# M112X.net
KiCad netlist of a schematic drawn in EAGLE
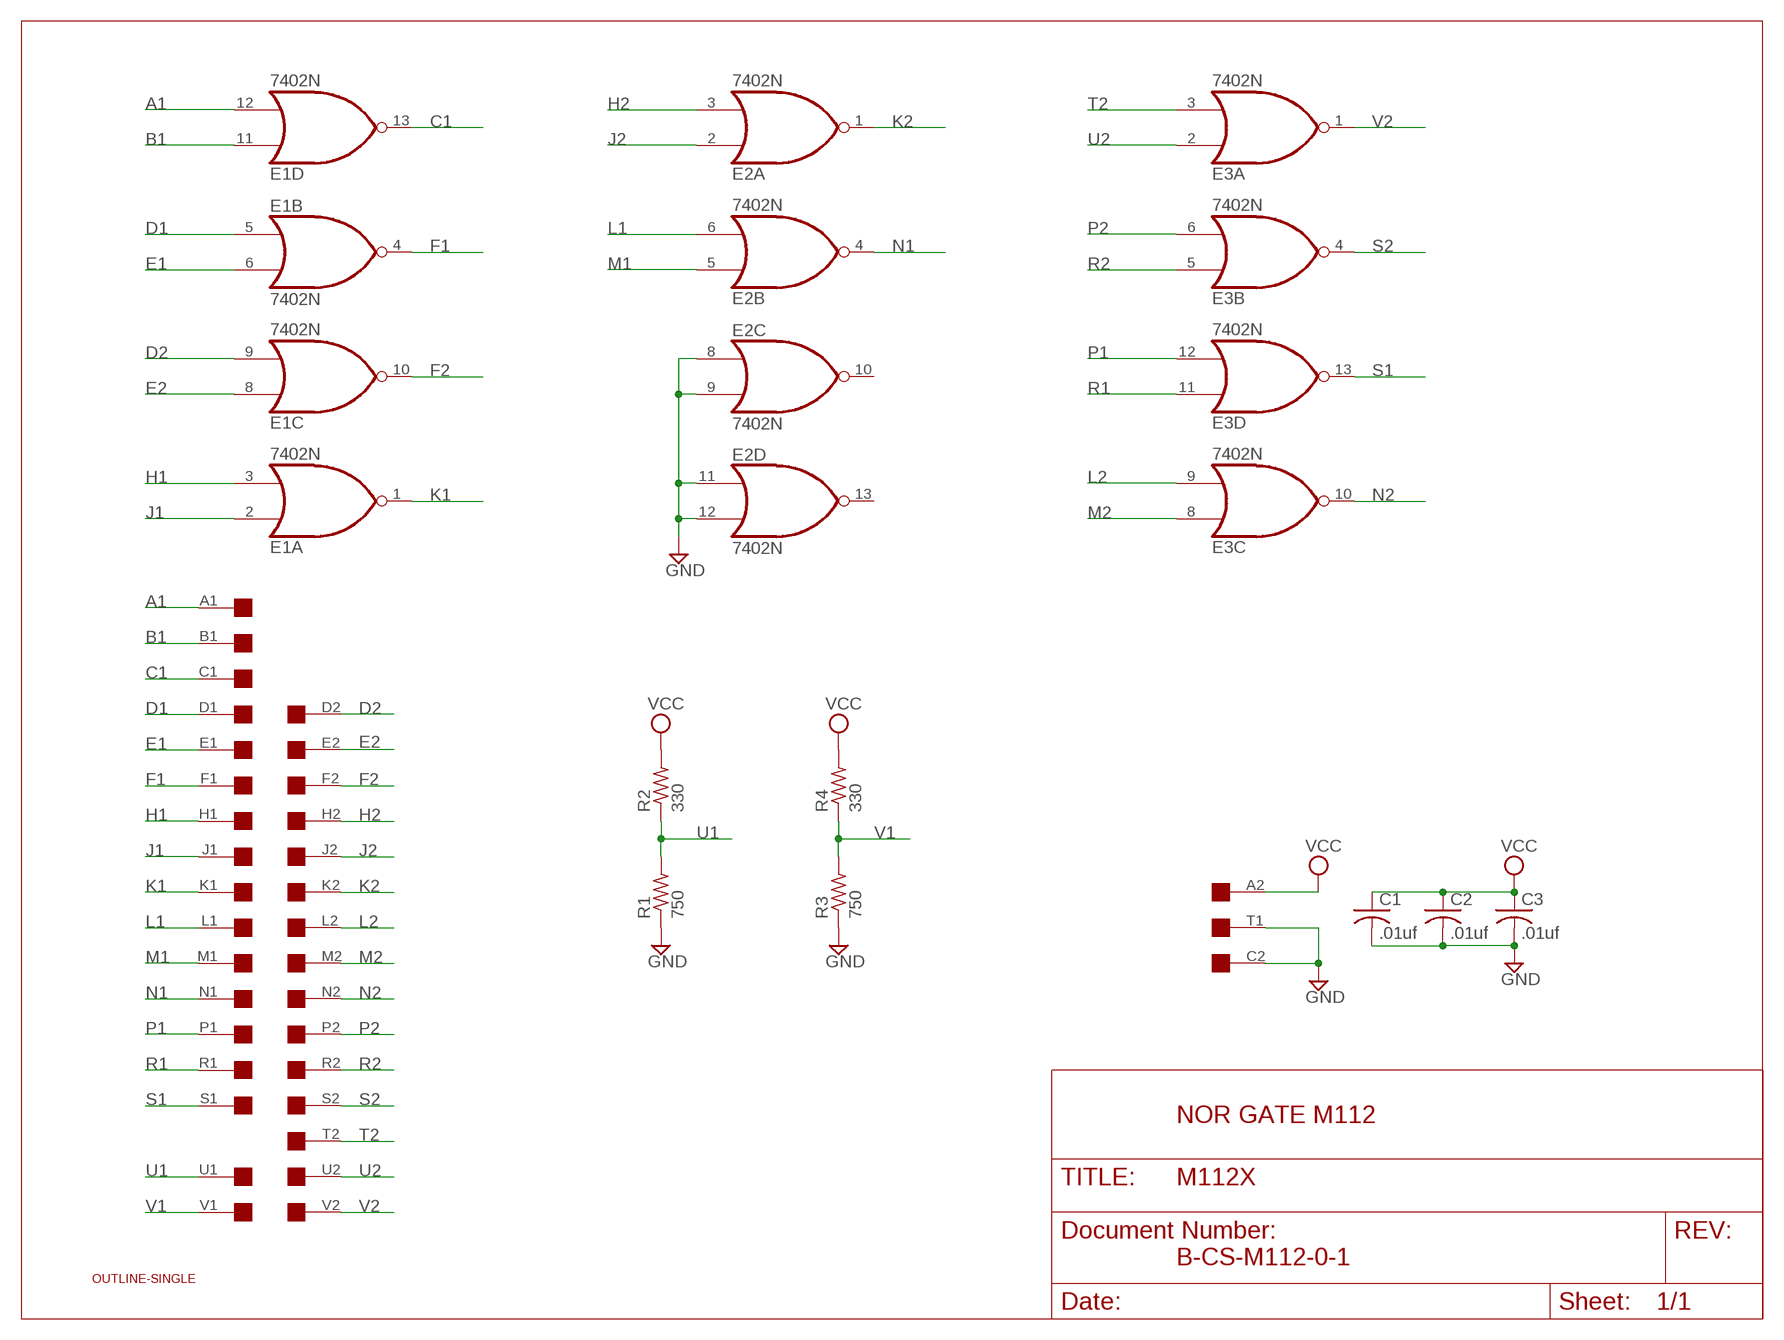
[diagram p0: schematic, sheet 1]

(export (version "E")
  (design (tool "Eeschema 10.0.6"))
  (components
    (comp (ref "C1")
      (value ".01uf")
      (footprint "eagle-import:C050-025X075")
      (libsource (lib "eagle-import") (part "C-US050-025X075"))
    )
    (comp (ref "C2")
      (value ".01uf")
      (footprint "eagle-import:C050-025X075")
      (libsource (lib "eagle-import") (part "C-US050-025X075"))
    )
    (comp (ref "C3")
      (value ".01uf")
      (footprint "eagle-import:C050-025X075")
      (libsource (lib "eagle-import") (part "C-US050-025X075"))
    )
    (comp (ref "E1")
      (value "7402N")
      (footprint "eagle-import:DIL14")
      (libsource (lib "eagle-import") (part "7402N"))
    )
    (comp (ref "E2")
      (value "7402N")
      (footprint "eagle-import:DIL14")
      (libsource (lib "eagle-import") (part "7402N"))
    )
    (comp (ref "E3")
      (value "7402N")
      (footprint "eagle-import:DIL14")
      (libsource (lib "eagle-import") (part "7402N"))
    )
    (comp (ref "R1")
      (value "750")
      (footprint "eagle-import:0207_10")
      (libsource (lib "eagle-import") (part "R-US_0207/10"))
    )
    (comp (ref "R2")
      (value "330")
      (footprint "eagle-import:0207_10")
      (libsource (lib "eagle-import") (part "R-US_0207/10"))
    )
    (comp (ref "R3")
      (value "750")
      (footprint "eagle-import:0207_10")
      (libsource (lib "eagle-import") (part "R-US_0207/10"))
    )
    (comp (ref "R4")
      (value "330")
      (footprint "eagle-import:0207_10")
      (libsource (lib "eagle-import") (part "R-US_0207/10"))
    )
    (comp (ref "U$1")
      (value "SINGLE")
      (footprint "eagle-import:EDGE-CON2")
      (libsource (lib "eagle-import") (part "SINGLE"))
    )
    (comp (ref "U$4")
      (value "OUTLINE-SINGLE")
      (footprint "eagle-import:SINGLE")
      (libsource (lib "eagle-import") (part "OUTLINE-SINGLE"))
    )
  )
  (nets
    (net (code "1") (name "/A1") (class "Default")
      (node (ref "E1") (pin "12") (pinfunction "I1_12") (pintype "input"))
      (node (ref "U$1") (pin "A1") (pinfunction "1_A1") (pintype "bidirectional"))
    )
    (net (code "2") (name "/B1") (class "Default")
      (node (ref "E1") (pin "11") (pinfunction "I0_11") (pintype "input"))
      (node (ref "U$1") (pin "B1") (pinfunction "1_B1") (pintype "bidirectional"))
    )
    (net (code "3") (name "/C1") (class "Default")
      (node (ref "E1") (pin "13") (pinfunction "O_13") (pintype "output"))
      (node (ref "U$1") (pin "C1") (pinfunction "1_C1") (pintype "bidirectional"))
    )
    (net (code "4") (name "/D1") (class "Default")
      (node (ref "E1") (pin "5") (pinfunction "I0_5") (pintype "input"))
      (node (ref "U$1") (pin "D1") (pinfunction "1_D1") (pintype "bidirectional"))
    )
    (net (code "5") (name "/D2") (class "Default")
      (node (ref "E1") (pin "9") (pinfunction "I1_9") (pintype "input"))
      (node (ref "U$1") (pin "D2") (pinfunction "1_D2") (pintype "bidirectional"))
    )
    (net (code "6") (name "/E1") (class "Default")
      (node (ref "E1") (pin "6") (pinfunction "I1_6") (pintype "input"))
      (node (ref "U$1") (pin "E1") (pinfunction "1_E1") (pintype "bidirectional"))
    )
    (net (code "7") (name "/E2") (class "Default")
      (node (ref "E1") (pin "8") (pinfunction "I0_8") (pintype "input"))
      (node (ref "U$1") (pin "E2") (pinfunction "1_E2") (pintype "bidirectional"))
    )
    (net (code "8") (name "/F1") (class "Default")
      (node (ref "E1") (pin "4") (pinfunction "O_4") (pintype "output"))
      (node (ref "U$1") (pin "F1") (pinfunction "1_F1") (pintype "bidirectional"))
    )
    (net (code "9") (name "/F2") (class "Default")
      (node (ref "E1") (pin "10") (pinfunction "O_10") (pintype "output"))
      (node (ref "U$1") (pin "F2") (pinfunction "1_F2") (pintype "bidirectional"))
    )
    (net (code "10") (name "/H1") (class "Default")
      (node (ref "E1") (pin "3") (pinfunction "I1_3") (pintype "input"))
      (node (ref "U$1") (pin "H1") (pinfunction "1_H1") (pintype "bidirectional"))
    )
    (net (code "11") (name "/H2") (class "Default")
      (node (ref "E2") (pin "3") (pinfunction "I1_3") (pintype "input"))
      (node (ref "U$1") (pin "H2") (pinfunction "1_H2") (pintype "bidirectional"))
    )
    (net (code "12") (name "/J1") (class "Default")
      (node (ref "E1") (pin "2") (pinfunction "I0_2") (pintype "input"))
      (node (ref "U$1") (pin "J1") (pinfunction "1_J1") (pintype "bidirectional"))
    )
    (net (code "13") (name "/J2") (class "Default")
      (node (ref "E2") (pin "2") (pinfunction "I0_2") (pintype "input"))
      (node (ref "U$1") (pin "J2") (pinfunction "1_J2") (pintype "bidirectional"))
    )
    (net (code "14") (name "/K1") (class "Default")
      (node (ref "E1") (pin "1") (pinfunction "O_1") (pintype "output"))
      (node (ref "U$1") (pin "K1") (pinfunction "1_K1") (pintype "bidirectional"))
    )
    (net (code "15") (name "/K2") (class "Default")
      (node (ref "E2") (pin "1") (pinfunction "O_1") (pintype "output"))
      (node (ref "U$1") (pin "K2") (pinfunction "1_K2") (pintype "bidirectional"))
    )
    (net (code "16") (name "/L1") (class "Default")
      (node (ref "E2") (pin "6") (pinfunction "I1_6") (pintype "input"))
      (node (ref "U$1") (pin "L1") (pinfunction "1_L1") (pintype "bidirectional"))
    )
    (net (code "17") (name "/L2") (class "Default")
      (node (ref "E3") (pin "9") (pinfunction "I1_9") (pintype "input"))
      (node (ref "U$1") (pin "L2") (pinfunction "1_L2") (pintype "bidirectional"))
    )
    (net (code "18") (name "/M1") (class "Default")
      (node (ref "E2") (pin "5") (pinfunction "I0_5") (pintype "input"))
      (node (ref "U$1") (pin "M1") (pinfunction "1_M1") (pintype "bidirectional"))
    )
    (net (code "19") (name "/M2") (class "Default")
      (node (ref "E3") (pin "8") (pinfunction "I0_8") (pintype "input"))
      (node (ref "U$1") (pin "M2") (pinfunction "1_M2") (pintype "bidirectional"))
    )
    (net (code "20") (name "/N1") (class "Default")
      (node (ref "E2") (pin "4") (pinfunction "O_4") (pintype "output"))
      (node (ref "U$1") (pin "N1") (pinfunction "1_N1") (pintype "bidirectional"))
    )
    (net (code "21") (name "/N2") (class "Default")
      (node (ref "E3") (pin "10") (pinfunction "O_10") (pintype "output"))
      (node (ref "U$1") (pin "N2") (pinfunction "1_N2") (pintype "bidirectional"))
    )
    (net (code "22") (name "/P1") (class "Default")
      (node (ref "E3") (pin "12") (pinfunction "I1_12") (pintype "input"))
      (node (ref "U$1") (pin "P1") (pinfunction "1_P1") (pintype "bidirectional"))
    )
    (net (code "23") (name "/P2") (class "Default")
      (node (ref "E3") (pin "6") (pinfunction "I1_6") (pintype "input"))
      (node (ref "U$1") (pin "P2") (pinfunction "1_P2") (pintype "bidirectional"))
    )
    (net (code "24") (name "/R1") (class "Default")
      (node (ref "E3") (pin "11") (pinfunction "I0_11") (pintype "input"))
      (node (ref "U$1") (pin "R1") (pinfunction "1_R1") (pintype "bidirectional"))
    )
    (net (code "25") (name "/R2") (class "Default")
      (node (ref "E3") (pin "5") (pinfunction "I0_5") (pintype "input"))
      (node (ref "U$1") (pin "R2") (pinfunction "1_R2") (pintype "bidirectional"))
    )
    (net (code "26") (name "/S1") (class "Default")
      (node (ref "E3") (pin "13") (pinfunction "O_13") (pintype "output"))
      (node (ref "U$1") (pin "S1") (pinfunction "1_S1") (pintype "bidirectional"))
    )
    (net (code "27") (name "/S2") (class "Default")
      (node (ref "E3") (pin "4") (pinfunction "O_4") (pintype "output"))
      (node (ref "U$1") (pin "S2") (pinfunction "1_S2") (pintype "bidirectional"))
    )
    (net (code "28") (name "/T2") (class "Default")
      (node (ref "E3") (pin "3") (pinfunction "I1_3") (pintype "input"))
      (node (ref "U$1") (pin "T2") (pinfunction "1_T2") (pintype "bidirectional"))
    )
    (net (code "29") (name "/U1") (class "Default")
      (node (ref "R1") (pin "2") (pinfunction "2_2") (pintype "passive"))
      (node (ref "R2") (pin "1") (pinfunction "1_1") (pintype "passive"))
      (node (ref "U$1") (pin "U1") (pinfunction "1_U1") (pintype "bidirectional"))
    )
    (net (code "30") (name "/U2") (class "Default")
      (node (ref "E3") (pin "2") (pinfunction "I0_2") (pintype "input"))
      (node (ref "U$1") (pin "U2") (pinfunction "1_U2") (pintype "bidirectional"))
    )
    (net (code "31") (name "/V1") (class "Default")
      (node (ref "R3") (pin "2") (pinfunction "2_2") (pintype "passive"))
      (node (ref "R4") (pin "1") (pinfunction "1_1") (pintype "passive"))
      (node (ref "U$1") (pin "V1") (pinfunction "1_V1") (pintype "bidirectional"))
    )
    (net (code "32") (name "/V2") (class "Default")
      (node (ref "E3") (pin "1") (pinfunction "O_1") (pintype "output"))
      (node (ref "U$1") (pin "V2") (pinfunction "1_V2") (pintype "bidirectional"))
    )
    (net (code "33") (name "GND") (class "Default")
      (node (ref "C1") (pin "2") (pinfunction "2_2") (pintype "passive"))
      (node (ref "C2") (pin "2") (pinfunction "2_2") (pintype "passive"))
      (node (ref "C3") (pin "2") (pinfunction "2_2") (pintype "passive"))
      (node (ref "E2") (pin "11") (pinfunction "I0_11") (pintype "input"))
      (node (ref "E2") (pin "12") (pinfunction "I1_12") (pintype "input"))
      (node (ref "E2") (pin "8") (pinfunction "I0_8") (pintype "input"))
      (node (ref "E2") (pin "9") (pinfunction "I1_9") (pintype "input"))
      (node (ref "R1") (pin "1") (pinfunction "1_1") (pintype "passive"))
      (node (ref "R3") (pin "1") (pinfunction "1_1") (pintype "passive"))
      (node (ref "U$1") (pin "C2") (pinfunction "1_C2") (pintype "bidirectional"))
      (node (ref "U$1") (pin "T1") (pinfunction "1_T1") (pintype "bidirectional"))
    )
    (net (code "34") (name "VCC") (class "Default")
      (node (ref "C1") (pin "1") (pinfunction "1_1") (pintype "passive"))
      (node (ref "C2") (pin "1") (pinfunction "1_1") (pintype "passive"))
      (node (ref "C3") (pin "1") (pinfunction "1_1") (pintype "passive"))
      (node (ref "R2") (pin "2") (pinfunction "2_2") (pintype "passive"))
      (node (ref "R4") (pin "2") (pinfunction "2_2") (pintype "passive"))
      (node (ref "U$1") (pin "A2") (pinfunction "1_A2") (pintype "bidirectional"))
    )
    (net (code "35") (name "unconnected-(E2C-O-Pad10)") (class "Default")
      (node (ref "E2") (pin "10") (pinfunction "O_10") (pintype "output"))
    )
    (net (code "36") (name "unconnected-(E2D-O-Pad13)") (class "Default")
      (node (ref "E2") (pin "13") (pinfunction "O_13") (pintype "output"))
    )
  )
)
